# Pressure_Converter.net
KiCad netlist of a schematic drawn in EAGLE
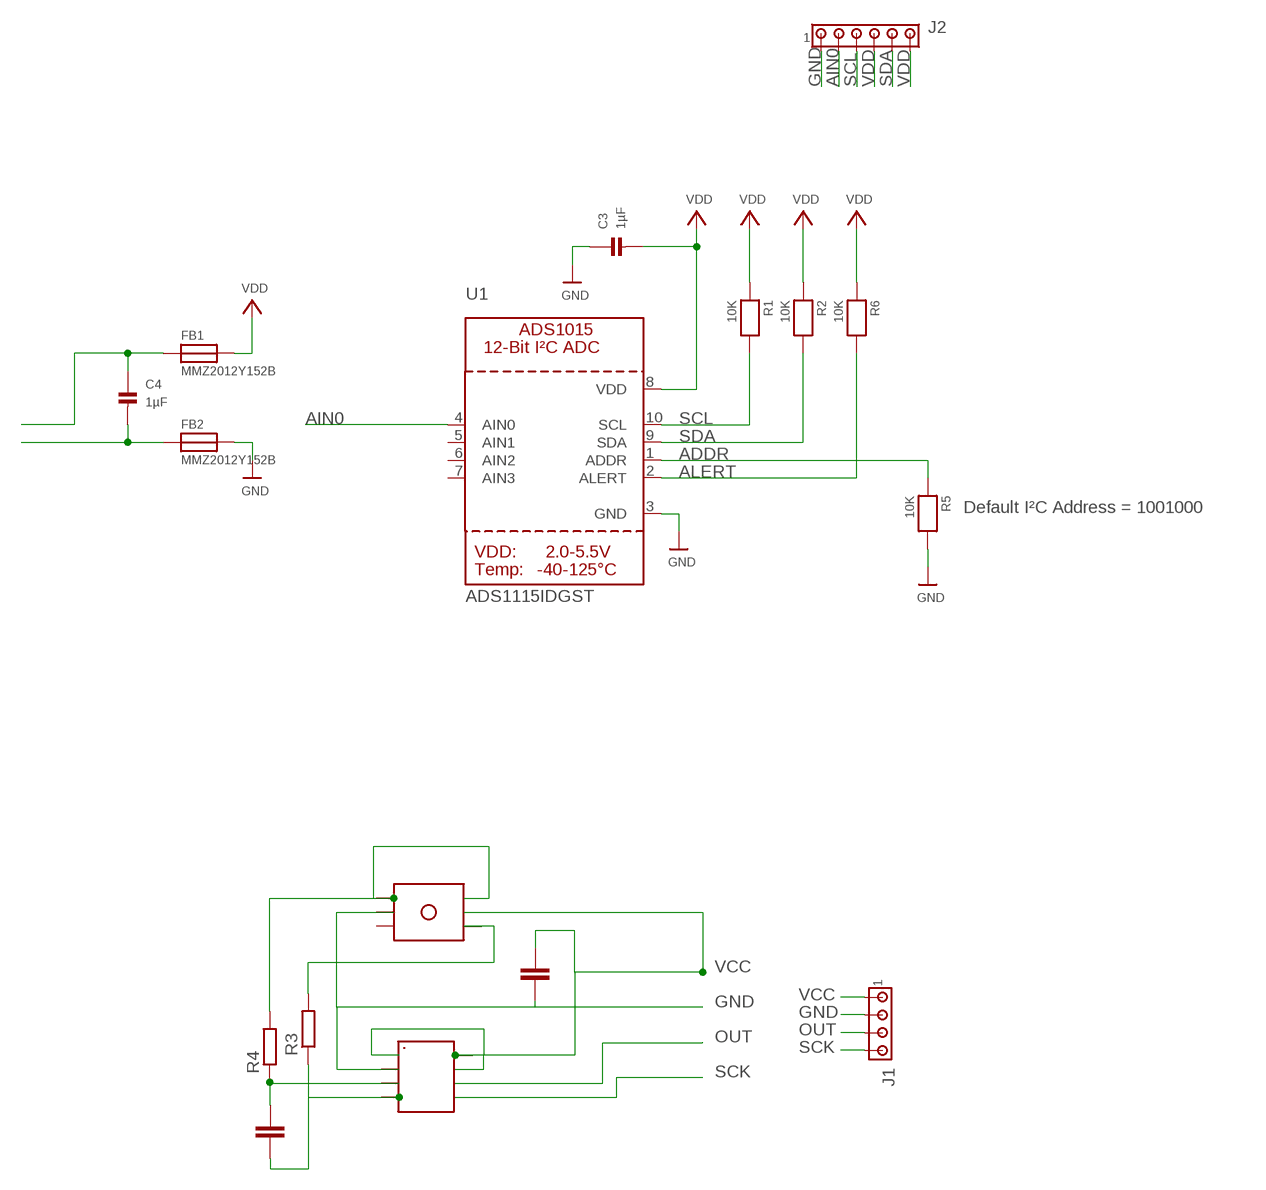
[diagram p0: schematic, sheet 1]

(export (version "E")
  (design (tool "Eeschema 10.0.6"))
  (components
    (comp (ref "C1")
      (value "100n")
      (footprint "eagle-import:C0805")
      (libsource (lib "eagle-import") (part "C-EUC0805"))
    )
    (comp (ref "C2")
      (value "100n")
      (footprint "eagle-import:C0805")
      (libsource (lib "eagle-import") (part "C-EUC0805"))
    )
    (comp (ref "C3")
      (value "1µF")
      (footprint "eagle-import:0805")
      (libsource (lib "eagle-import") (part "CAP_CERAMIC0805"))
    )
    (comp (ref "C4")
      (value "1µF")
      (footprint "eagle-import:0805")
      (libsource (lib "eagle-import") (part "CAP_CERAMIC0805"))
    )
    (comp (ref "FB1")
      (value "MMZ2012Y152B")
      (footprint "eagle-import:0805")
      (libsource (lib "eagle-import") (part "FERRITE0805"))
    )
    (comp (ref "FB2")
      (value "MMZ2012Y152B")
      (footprint "eagle-import:0805")
      (libsource (lib "eagle-import") (part "FERRITE0805"))
    )
    (comp (ref "J1")
      (value "MTA04-100")
      (footprint "eagle-import:10X04MTA")
      (libsource (lib "eagle-import") (part "MTA04-100"))
    )
    (comp (ref "J2")
      (value "MTA06-156")
      (footprint "eagle-import:1X6MTA")
      (libsource (lib "eagle-import") (part "MTA06-156"))
    )
    (comp (ref "R1")
      (value "10K")
      (footprint "eagle-import:0805")
      (libsource (lib "eagle-import") (part "RESISTOR0805"))
    )
    (comp (ref "R2")
      (value "10K")
      (footprint "eagle-import:0805")
      (libsource (lib "eagle-import") (part "RESISTOR0805"))
    )
    (comp (ref "R3")
      (value "R-EU_R0805")
      (footprint "eagle-import:R0805")
      (libsource (lib "eagle-import") (part "R-EU_R0805"))
    )
    (comp (ref "R4")
      (value "R-EU_R0805")
      (footprint "eagle-import:R0805")
      (libsource (lib "eagle-import") (part "R-EU_R0805"))
    )
    (comp (ref "R5")
      (value "10K")
      (footprint "eagle-import:0805")
      (libsource (lib "eagle-import") (part "RESISTOR0805"))
    )
    (comp (ref "R6")
      (value "10K")
      (footprint "eagle-import:0805")
      (libsource (lib "eagle-import") (part "RESISTOR0805"))
    )
    (comp (ref "U$1")
      (value "HX710B")
      (footprint "eagle-import:HX710B")
      (libsource (lib "eagle-import") (part "HX710B"))
    )
    (comp (ref "U$2")
      (value "PRESSURE")
      (footprint "eagle-import:PRESSURE")
      (libsource (lib "eagle-import") (part "PRESSURE"))
    )
    (comp (ref "U1")
      (value "ADS1115IDGST")
      (footprint "eagle-import:MSOP10")
      (libsource (lib "eagle-import") (part "ADC_ADS1015"))
    )
  )
  (nets
    (net (code "1") (name "/ADDR") (class "Default")
      (node (ref "R5") (pin "1") (pinfunction "1_1") (pintype "passive"))
      (node (ref "U1") (pin "1") (pinfunction "ADDR_1") (pintype "bidirectional"))
    )
    (net (code "2") (name "/AIN0") (class "Default")
      (node (ref "J2") (pin "2") (pinfunction "2_2") (pintype "passive"))
      (node (ref "U1") (pin "4") (pinfunction "AIN0_4") (pintype "bidirectional"))
    )
    (net (code "3") (name "/ALERT") (class "Default")
      (node (ref "R6") (pin "2") (pinfunction "2_2") (pintype "passive"))
      (node (ref "U1") (pin "2") (pinfunction "ALERT_2") (pintype "bidirectional"))
    )
    (net (code "4") (name "/OUT") (class "Default")
      (node (ref "J1") (pin "3") (pinfunction "3_3") (pintype "passive"))
      (node (ref "U$1") (pin "DOUT") (pinfunction "DOUT_DOUT") (pintype "bidirectional"))
    )
    (net (code "5") (name "/SCK") (class "Default")
      (node (ref "J1") (pin "4") (pinfunction "4_4") (pintype "passive"))
      (node (ref "U$1") (pin "SCK") (pinfunction "SCK_SCK") (pintype "bidirectional"))
    )
    (net (code "6") (name "/SCL") (class "Default")
      (node (ref "J2") (pin "3") (pinfunction "3_3") (pintype "passive"))
      (node (ref "R1") (pin "2") (pinfunction "2_2") (pintype "passive"))
      (node (ref "U1") (pin "10") (pinfunction "SCL_10") (pintype "bidirectional"))
    )
    (net (code "7") (name "/SDA") (class "Default")
      (node (ref "J2") (pin "5") (pinfunction "5_5") (pintype "passive"))
      (node (ref "R2") (pin "2") (pinfunction "2_2") (pintype "passive"))
      (node (ref "U1") (pin "9") (pinfunction "SDA_9") (pintype "bidirectional"))
    )
    (net (code "8") (name "/VCC") (class "Default")
      (node (ref "C1") (pin "1") (pinfunction "1_1") (pintype "passive"))
      (node (ref "J1") (pin "1") (pinfunction "1_1") (pintype "passive"))
      (node (ref "U$1") (pin "AVDD") (pinfunction "AVDD_AVDD") (pintype "bidirectional"))
      (node (ref "U$1") (pin "DVDD") (pinfunction "DVDD_DVDD") (pintype "bidirectional"))
      (node (ref "U$1") (pin "VREF") (pinfunction "VREF_VREF") (pintype "bidirectional"))
      (node (ref "U$2") (pin "5") (pinfunction "5_5") (pintype "bidirectional"))
    )
    (net (code "9") (name "GND") (class "Default")
      (node (ref "C1") (pin "2") (pinfunction "2_2") (pintype "passive"))
      (node (ref "C3") (pin "1") (pinfunction "P$1_1") (pintype "passive"))
      (node (ref "FB2") (pin "2") (pinfunction "P$2_2") (pintype "bidirectional"))
      (node (ref "J1") (pin "2") (pinfunction "2_2") (pintype "passive"))
      (node (ref "J2") (pin "1") (pinfunction "1_1") (pintype "passive"))
      (node (ref "R5") (pin "2") (pinfunction "2_2") (pintype "passive"))
      (node (ref "U$1") (pin "AGND") (pinfunction "AGND_AGND") (pintype "bidirectional"))
      (node (ref "U$2") (pin "2") (pinfunction "2_2") (pintype "bidirectional"))
      (node (ref "U1") (pin "3") (pinfunction "GND_3") (pintype "bidirectional"))
    )
    (net (code "10") (name "Net-(C2-Pad1)") (class "Default")
      (node (ref "C2") (pin "1") (pinfunction "1_1") (pintype "passive"))
      (node (ref "R3") (pin "1") (pinfunction "1_1") (pintype "passive"))
      (node (ref "U$1") (pin "INP") (pinfunction "INP_INP") (pintype "bidirectional"))
    )
    (net (code "11") (name "Net-(C2-Pad2)") (class "Default")
      (node (ref "C2") (pin "2") (pinfunction "2_2") (pintype "passive"))
      (node (ref "R4") (pin "1") (pinfunction "1_1") (pintype "passive"))
      (node (ref "U$1") (pin "INN") (pinfunction "INN_INN") (pintype "bidirectional"))
    )
    (net (code "12") (name "Net-(C4-P$1)") (class "Default")
      (node (ref "C4") (pin "1") (pinfunction "P$1_1") (pintype "passive"))
      (node (ref "FB1") (pin "1") (pinfunction "P$1_1") (pintype "bidirectional"))
    )
    (net (code "13") (name "Net-(C4-P$2)") (class "Default")
      (node (ref "C4") (pin "2") (pinfunction "P$2_2") (pintype "passive"))
      (node (ref "FB2") (pin "1") (pinfunction "P$1_1") (pintype "bidirectional"))
    )
    (net (code "14") (name "Net-(R3-Pad2)") (class "Default")
      (node (ref "R3") (pin "2") (pinfunction "2_2") (pintype "passive"))
      (node (ref "U$2") (pin "4") (pinfunction "4_4") (pintype "bidirectional"))
    )
    (net (code "15") (name "Net-(R4-Pad2)") (class "Default")
      (node (ref "R4") (pin "2") (pinfunction "2_2") (pintype "passive"))
      (node (ref "U$2") (pin "1") (pinfunction "1_1") (pintype "bidirectional"))
      (node (ref "U$2") (pin "6") (pinfunction "6_6") (pintype "bidirectional"))
    )
    (net (code "16") (name "VDD") (class "Default")
      (node (ref "C3") (pin "2") (pinfunction "P$2_2") (pintype "passive"))
      (node (ref "FB1") (pin "2") (pinfunction "P$2_2") (pintype "bidirectional"))
      (node (ref "J2") (pin "4") (pinfunction "4_4") (pintype "passive"))
      (node (ref "J2") (pin "6") (pinfunction "6_6") (pintype "passive"))
      (node (ref "R1") (pin "1") (pinfunction "1_1") (pintype "passive"))
      (node (ref "R2") (pin "1") (pinfunction "1_1") (pintype "passive"))
      (node (ref "R6") (pin "1") (pinfunction "1_1") (pintype "passive"))
      (node (ref "U1") (pin "8") (pinfunction "VDD_8") (pintype "bidirectional"))
    )
    (net (code "17") (name "unconnected-(U$2-Pad3)") (class "Default")
      (node (ref "U$2") (pin "3") (pinfunction "3_3") (pintype "bidirectional"))
    )
    (net (code "18") (name "unconnected-(U1-AIN1-Pad5)") (class "Default")
      (node (ref "U1") (pin "5") (pinfunction "AIN1_5") (pintype "bidirectional"))
    )
    (net (code "19") (name "unconnected-(U1-AIN2-Pad6)") (class "Default")
      (node (ref "U1") (pin "6") (pinfunction "AIN2_6") (pintype "bidirectional"))
    )
    (net (code "20") (name "unconnected-(U1-AIN3-Pad7)") (class "Default")
      (node (ref "U1") (pin "7") (pinfunction "AIN3_7") (pintype "bidirectional"))
    )
  )
)
